# shema.net
KiCad netlist of a schematic drawn in Altium Designer
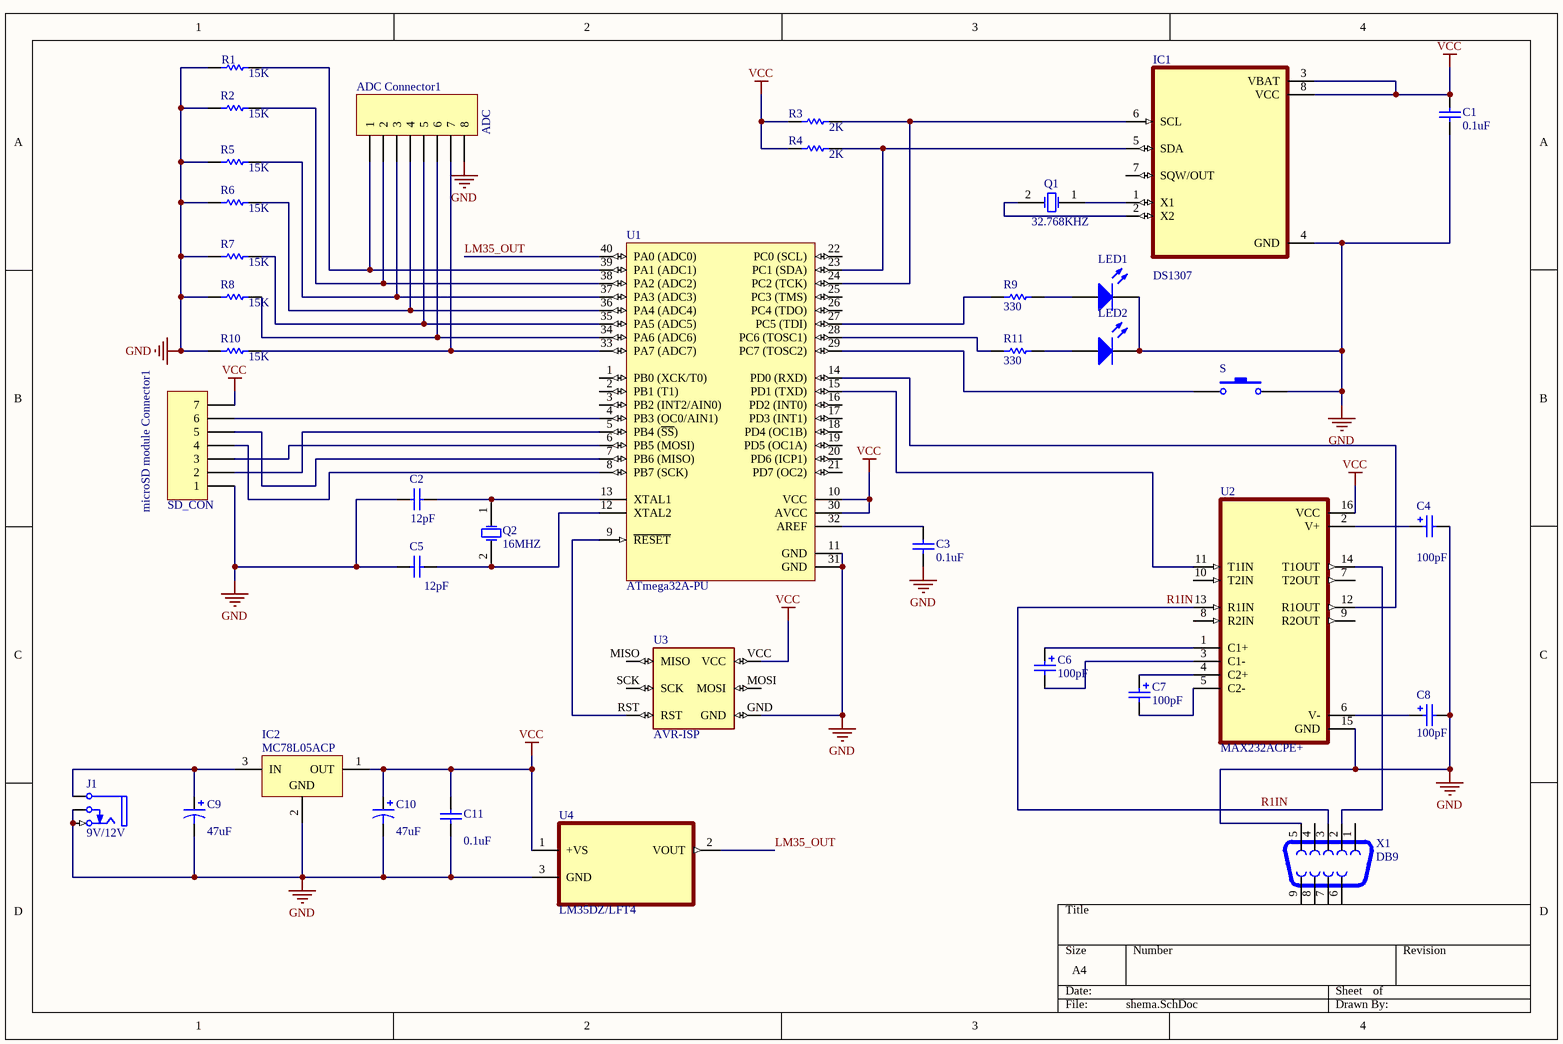
[diagram p0: shema.SchDoc]

(export (version "E")
  (design (tool "Eeschema 10.0.6"))
  (components
    (comp (ref "ADC Connector1")
      (value "ADC")
      (footprint "HDR1X8")
      (description "Header, 8-Pin")
      (fields (field (name "PUBLISHER") "Altium Limited"))
      (libsource (lib "Miscellaneous Connectors") (part "Header 8"))
    )
    (comp (ref "C1")
      (value "0.1uF")
      (footprint "RAD-0.3")
      (description "Capacitor")
      (fields (field (name "Comment") "Cap") (field (name "PUBLISHER") "Altium Limited"))
      (libsource (lib "Miscellaneous Devices") (part "Cap"))
    )
    (comp (ref "C2")
      (value "12pF")
      (footprint "RAD-0.3")
      (description "Capacitor")
      (fields (field (name "Comment") "Cap") (field (name "PUBLISHER") "Altium Limited"))
      (libsource (lib "Miscellaneous Devices") (part "Cap"))
    )
    (comp (ref "C3")
      (value "0.1uF")
      (footprint "RAD-0.3")
      (description "Capacitor")
      (fields (field (name "Comment") "Cap") (field (name "PUBLISHER") "Altium Limited"))
      (libsource (lib "Miscellaneous Devices") (part "Cap"))
    )
    (comp (ref "C4")
      (value "100pF")
      (footprint "POLAR0.8")
      (description "Polarized Capacitor (Axial)")
      (fields (field (name "Comment") "Cap Pol2") (field (name "PUBLISHER") "Altium Limited"))
      (libsource (lib "Miscellaneous Devices") (part "Cap Pol2"))
    )
    (comp (ref "C5")
      (value "12pF")
      (footprint "RAD-0.3")
      (description "Capacitor")
      (fields (field (name "Comment") "Cap") (field (name "PUBLISHER") "Altium Limited"))
      (libsource (lib "Miscellaneous Devices") (part "Cap"))
    )
    (comp (ref "C6")
      (value "100pF")
      (footprint "POLAR0.8")
      (description "Polarized Capacitor (Axial)")
      (fields (field (name "Comment") "Cap Pol2") (field (name "PUBLISHER") "Altium Limited"))
      (libsource (lib "Miscellaneous Devices") (part "Cap Pol2"))
    )
    (comp (ref "C7")
      (value "100pF")
      (footprint "POLAR0.8")
      (description "Polarized Capacitor (Axial)")
      (fields (field (name "Comment") "Cap Pol2") (field (name "PUBLISHER") "Altium Limited"))
      (libsource (lib "Miscellaneous Devices") (part "Cap Pol2"))
    )
    (comp (ref "C8")
      (value "100pF")
      (footprint "POLAR0.8")
      (description "Polarized Capacitor (Axial)")
      (fields (field (name "Comment") "Cap Pol2") (field (name "PUBLISHER") "Altium Limited"))
      (libsource (lib "Miscellaneous Devices") (part "Cap Pol2"))
    )
    (comp (ref "C9")
      (value "47uF")
      (footprint "RB7.6-15")
      (description "Polarized Capacitor (Radial)")
      (fields (field (name "Comment") "Cap Pol1") (field (name "PUBLISHER") "Altium Limited"))
      (libsource (lib "Miscellaneous Devices") (part "Cap Pol1"))
    )
    (comp (ref "C10")
      (value "47uF")
      (footprint "RB7.6-15")
      (description "Polarized Capacitor (Radial)")
      (fields (field (name "Comment") "Cap Pol1") (field (name "PUBLISHER") "Altium Limited"))
      (libsource (lib "Miscellaneous Devices") (part "Cap Pol1"))
    )
    (comp (ref "C11")
      (value "0.1uF")
      (footprint "RAD-0.3")
      (description "Capacitor")
      (fields (field (name "Comment") "Cap") (field (name "PUBLISHER") "Altium Limited"))
      (libsource (lib "Miscellaneous Devices") (part "Cap"))
    )
    (comp (ref "IC1")
      (value "DS1307")
      (footprint "DIP794W47P254L991H457Q8")
      (description "Real Time Clock (RTC) IC Clock/Calendar 56B IÂ²C, 2-Wire Serial 8-SOIC (0.154, 3.90mm Width)")
      (fields (field (name "MF") "Maxim Integrated"))
      (libsource (lib "DS1307") (part "DS1307"))
    )
    (comp (ref "IC2")
      (value "MC78L05ACP")
      (footprint "29-04")
      (description "3-Terminal Low-Current Positive Fixed Voltage Regulator")
      (fields (field (name "PUBLISHER") "Altium Limited"))
      (libsource (lib "Motorola Power Mgt Voltage Regulator") (part "MC78L05ACP"))
    )
    (comp (ref "J1")
      (value "9V/12V")
      (footprint "JACK/6-V3A")
      (description "Jack Socket, 1/4\" [6.5mm], Thru-Hole, Vertical, 2-Conductor with Tip closed")
      (fields (field (name "PUBLISHER") "Altium Limited"))
      (libsource (lib "Miscellaneous Connectors") (part "Phonejack2 TN"))
    )
    (comp (ref "LED1")
      (value "LED0")
      (footprint "LED-0")
      (description "Typical INFRARED GaAs LED")
      (fields (field (name "PUBLISHER") "Altium Limited"))
      (libsource (lib "Miscellaneous Devices") (part "LED0"))
    )
    (comp (ref "LED2")
      (value "LED0")
      (footprint "LED-0")
      (description "Typical INFRARED GaAs LED")
      (fields (field (name "PUBLISHER") "Altium Limited"))
      (libsource (lib "Miscellaneous Devices") (part "LED0"))
    )
    (comp (ref "microSD module Connector1")
      (value "SD_CON")
      (footprint "HDR1X7")
      (description "Header, 7-Pin")
      (fields (field (name "PUBLISHER") "Altium Limited"))
      (libsource (lib "Miscellaneous Connectors") (part "Header 7"))
    )
    (comp (ref "Q1")
      (value "XTAL")
      (footprint "R38")
      (description "Crystal Oscillator")
      (fields (field (name "FREQ") "32.768KHZ") (field (name "PUBLISHER") "Altium Limited"))
      (libsource (lib "Miscellaneous Devices") (part "XTAL"))
    )
    (comp (ref "Q2")
      (value "XTAL")
      (footprint "R38")
      (description "Crystal Oscillator")
      (fields (field (name "FREQ") "16MHZ") (field (name "PUBLISHER") "Altium Limited"))
      (libsource (lib "Miscellaneous Devices") (part "XTAL"))
    )
    (comp (ref "R1")
      (value "15K")
      (footprint "AXIAL-0.3")
      (description "Resistor")
      (fields (field (name "Comment") "Res1") (field (name "PUBLISHER") "Altium Limited"))
      (libsource (lib "Miscellaneous Devices") (part "Res1"))
    )
    (comp (ref "R2")
      (value "15K")
      (footprint "AXIAL-0.3")
      (description "Resistor")
      (fields (field (name "Comment") "Res1") (field (name "PUBLISHER") "Altium Limited"))
      (libsource (lib "Miscellaneous Devices") (part "Res1"))
    )
    (comp (ref "R3")
      (value "2K")
      (footprint "AXIAL-0.3")
      (description "Resistor")
      (fields (field (name "Comment") "Res1") (field (name "PUBLISHER") "Altium Limited"))
      (libsource (lib "Miscellaneous Devices") (part "Res1"))
    )
    (comp (ref "R4")
      (value "2K")
      (footprint "AXIAL-0.3")
      (description "Resistor")
      (fields (field (name "Comment") "Res1") (field (name "PUBLISHER") "Altium Limited"))
      (libsource (lib "Miscellaneous Devices") (part "Res1"))
    )
    (comp (ref "R5")
      (value "15K")
      (footprint "AXIAL-0.3")
      (description "Resistor")
      (fields (field (name "Comment") "Res1") (field (name "PUBLISHER") "Altium Limited"))
      (libsource (lib "Miscellaneous Devices") (part "Res1"))
    )
    (comp (ref "R6")
      (value "15K")
      (footprint "AXIAL-0.3")
      (description "Resistor")
      (fields (field (name "Comment") "Res1") (field (name "PUBLISHER") "Altium Limited"))
      (libsource (lib "Miscellaneous Devices") (part "Res1"))
    )
    (comp (ref "R7")
      (value "15K")
      (footprint "AXIAL-0.3")
      (description "Resistor")
      (fields (field (name "Comment") "Res1") (field (name "PUBLISHER") "Altium Limited"))
      (libsource (lib "Miscellaneous Devices") (part "Res1"))
    )
    (comp (ref "R8")
      (value "15K")
      (footprint "AXIAL-0.3")
      (description "Resistor")
      (fields (field (name "Comment") "Res1") (field (name "PUBLISHER") "Altium Limited"))
      (libsource (lib "Miscellaneous Devices") (part "Res1"))
    )
    (comp (ref "R9")
      (value "330")
      (footprint "AXIAL-0.3")
      (description "Resistor")
      (fields (field (name "Comment") "Res1") (field (name "PUBLISHER") "Altium Limited"))
      (libsource (lib "Miscellaneous Devices") (part "Res1"))
    )
    (comp (ref "R10")
      (value "15K")
      (footprint "AXIAL-0.3")
      (description "Resistor")
      (fields (field (name "Comment") "Res1") (field (name "PUBLISHER") "Altium Limited"))
      (libsource (lib "Miscellaneous Devices") (part "Res1"))
    )
    (comp (ref "R11")
      (value "330")
      (footprint "AXIAL-0.3")
      (description "Resistor")
      (fields (field (name "Comment") "Res1") (field (name "PUBLISHER") "Altium Limited"))
      (libsource (lib "Miscellaneous Devices") (part "Res1"))
    )
    (comp (ref "S")
      (value "SW-PB")
      (footprint "SPST-2")
      (description "Switch")
      (fields (field (name "PUBLISHER") "Altium Limited"))
      (libsource (lib "Miscellaneous Devices") (part "SW-PB"))
    )
    (comp (ref "U1")
      (value "ATmega32A-PU")
      (footprint "40P6")
      (fields (field (name "PUBLISHER") "Altium Limited"))
      (libsource (lib "Atmel Microcontroller 8-Bit megaAVR") (part "ATmega32A-PU"))
    )
    (comp (ref "U2")
      (value "MAX232ACPE+")
      (footprint "DIP794W47P254L1943H457Q16")
      (description "2/2 Transceiver Full RS232 16-PDIP")
      (fields (field (name "MP") "MAX232ACPE") (field (name "MF") "Maxim Integrated"))
      (libsource (lib "MAX232ACPE_") (part "MAX232ACPE+"))
    )
    (comp (ref "U3")
      (value "AVR-ISP")
      (footprint "AVR-ISP")
      (description "Emulators / Simulators AVR USB IN CIRCUIT EMUL/PRGMR ISP")
      (fields (field (name "MF") "Gravitech"))
      (libsource (lib "AVR-ISP") (part "AVR-ISP"))
    )
    (comp (ref "U4")
      (value "LM35DZ/LFT4")
      (footprint "TO127P254X495-3P")
      (description "&plusmn;0.5&deg;C 4V-30V, Temperature sensor with analog output 3-TO-92")
      (fields
        (field (name "MF") "Texas Instruments")
        (field (name "BUYPART") "https://www.snapeda.com/parts/LM35DZ/LFT4/Texas%20Instruments/view-part/19434/?ref=eda")
      )
      (libsource (lib "LM35DZ_LFT4") (part "LM35DZ/LFT4"))
    )
    (comp (ref "X1")
      (value "DB9")
      (footprint "DB9")
      (description "SURGE SUPPRESSOR RS-232 DB9M/F")
      (fields (field (name "MF") "Tripp Lite"))
      (libsource (lib "DB9") (part "DB9"))
    )
  )
  (nets
    (net (code "1") (name "/LM35_OUT") (class "Default")
      (node (ref "U1") (pin "40") (pinfunction "PA0_(ADC0)_40") (pintype "bidirectional"))
      (node (ref "U4") (pin "2") (pinfunction "VOUT_2") (pintype "output"))
    )
    (net (code "2") (name "/R1IN") (class "Default")
      (node (ref "U2") (pin "13") (pinfunction "R1IN_13") (pintype "input"))
      (node (ref "X1") (pin "3") (pinfunction "3_3") (pintype "passive"))
    )
    (net (code "3") (name "GND") (class "Default")
      (node (ref "ADC Connector1") (pin "8") (pinfunction "8_8") (pintype "passive"))
      (node (ref "C1") (pin "1") (pinfunction "1_1") (pintype "passive"))
      (node (ref "C10") (pin "2") (pinfunction "2_2") (pintype "passive"))
      (node (ref "C11") (pin "1") (pinfunction "1_1") (pintype "passive"))
      (node (ref "C2") (pin "1") (pinfunction "1_1") (pintype "passive"))
      (node (ref "C3") (pin "2") (pinfunction "2_2") (pintype "passive"))
      (node (ref "C4") (pin "2") (pinfunction "2_2") (pintype "passive"))
      (node (ref "C5") (pin "1") (pinfunction "1_1") (pintype "passive"))
      (node (ref "C8") (pin "2") (pinfunction "2_2") (pintype "passive"))
      (node (ref "C9") (pin "2") (pinfunction "2_2") (pintype "passive"))
      (node (ref "IC1") (pin "4") (pinfunction "GND_4") (pintype "power_in"))
      (node (ref "IC2") (pin "2") (pinfunction "GND_2") (pintype "power_in"))
      (node (ref "J1") (pin "1") (pinfunction "T_1") (pintype "input"))
      (node (ref "J1") (pin "2") (pinfunction "TN_2") (pintype "passive"))
      (node (ref "LED1") (pin "2") (pinfunction "K_2") (pintype "passive"))
      (node (ref "LED2") (pin "2") (pinfunction "K_2") (pintype "passive"))
      (node (ref "R1") (pin "1") (pinfunction "1_1") (pintype "passive"))
      (node (ref "R10") (pin "1") (pinfunction "1_1") (pintype "passive"))
      (node (ref "R2") (pin "1") (pinfunction "1_1") (pintype "passive"))
      (node (ref "R5") (pin "1") (pinfunction "1_1") (pintype "passive"))
      (node (ref "R6") (pin "1") (pinfunction "1_1") (pintype "passive"))
      (node (ref "R7") (pin "1") (pinfunction "1_1") (pintype "passive"))
      (node (ref "R8") (pin "1") (pinfunction "1_1") (pintype "passive"))
      (node (ref "S") (pin "2") (pinfunction "2_2") (pintype "passive"))
      (node (ref "U1") (pin "11") (pinfunction "GND_11") (pintype "power_in"))
      (node (ref "U1") (pin "31") (pinfunction "GND_31") (pintype "power_in"))
      (node (ref "U2") (pin "15") (pinfunction "GND_15") (pintype "power_in"))
      (node (ref "U3") (pin "GND") (pinfunction "GND_GND") (pintype "bidirectional"))
      (node (ref "U4") (pin "3") (pinfunction "GND_3") (pintype "passive"))
      (node (ref "X1") (pin "5") (pinfunction "5_5") (pintype "passive"))
      (node (ref "microSD module Connector1") (pin "1") (pinfunction "1_1") (pintype "passive"))
    )
    (net (code "4") (name "Net-(IC1-SCL)") (class "Default")
      (node (ref "IC1") (pin "6") (pinfunction "SCL_6") (pintype "input"))
      (node (ref "R3") (pin "2") (pinfunction "2_2") (pintype "passive"))
      (node (ref "U1") (pin "24") (pinfunction "PC2_(TCK)_24") (pintype "bidirectional"))
    )
    (net (code "5") (name "Net-(IC1-SDA)") (class "Default")
      (node (ref "IC1") (pin "5") (pinfunction "SDA_5") (pintype "bidirectional"))
      (node (ref "R4") (pin "2") (pinfunction "2_2") (pintype "passive"))
      (node (ref "U1") (pin "23") (pinfunction "PC1_(SDA)_23") (pintype "bidirectional"))
    )
    (net (code "6") (name "Net-(IC1-X1)") (class "Default")
      (node (ref "IC1") (pin "1") (pinfunction "X1_1") (pintype "bidirectional"))
      (node (ref "Q1") (pin "1") (pinfunction "OSC1_1") (pintype "passive"))
    )
    (net (code "7") (name "Net-(IC1-X2)") (class "Default")
      (node (ref "IC1") (pin "2") (pinfunction "X2_2") (pintype "bidirectional"))
      (node (ref "Q1") (pin "2") (pinfunction "OSC2_2") (pintype "passive"))
    )
    (net (code "8") (name "Net-(IC2-IN)") (class "Default")
      (node (ref "C9") (pin "1") (pinfunction "1_1") (pintype "passive"))
      (node (ref "IC2") (pin "3") (pinfunction "IN_3") (pintype "power_in"))
      (node (ref "J1") (pin "5") (pinfunction "S_5") (pintype "power_in"))
    )
    (net (code "9") (name "Net-(LED1-A)") (class "Default")
      (node (ref "LED1") (pin "1") (pinfunction "A_1") (pintype "passive"))
      (node (ref "R9") (pin "2") (pinfunction "2_2") (pintype "passive"))
    )
    (net (code "10") (name "Net-(LED2-A)") (class "Default")
      (node (ref "LED2") (pin "1") (pinfunction "A_1") (pintype "passive"))
      (node (ref "R11") (pin "2") (pinfunction "2_2") (pintype "passive"))
    )
    (net (code "11") (name "Net-(Q2-OSC1)") (class "Default")
      (node (ref "C2") (pin "2") (pinfunction "2_2") (pintype "passive"))
      (node (ref "Q2") (pin "1") (pinfunction "OSC1_1") (pintype "passive"))
      (node (ref "U1") (pin "13") (pinfunction "XTAL1_13") (pintype "passive"))
    )
    (net (code "12") (name "Net-(Q2-OSC2)") (class "Default")
      (node (ref "C5") (pin "2") (pinfunction "2_2") (pintype "passive"))
      (node (ref "Q2") (pin "2") (pinfunction "OSC2_2") (pintype "passive"))
      (node (ref "U1") (pin "12") (pinfunction "XTAL2_12") (pintype "passive"))
    )
    (net (code "13") (name "Net-(U1-AREF)") (class "Default")
      (node (ref "C3") (pin "1") (pinfunction "1_1") (pintype "passive"))
      (node (ref "U1") (pin "32") (pinfunction "AREF_32") (pintype "power_in"))
    )
    (net (code "14") (name "Net-(U1-PA1_(ADC1))") (class "Default")
      (node (ref "ADC Connector1") (pin "1") (pinfunction "1_1") (pintype "passive"))
      (node (ref "R1") (pin "2") (pinfunction "2_2") (pintype "passive"))
      (node (ref "U1") (pin "39") (pinfunction "PA1_(ADC1)_39") (pintype "bidirectional"))
    )
    (net (code "15") (name "Net-(U1-PA2_(ADC2))") (class "Default")
      (node (ref "ADC Connector1") (pin "2") (pinfunction "2_2") (pintype "passive"))
      (node (ref "R2") (pin "2") (pinfunction "2_2") (pintype "passive"))
      (node (ref "U1") (pin "38") (pinfunction "PA2_(ADC2)_38") (pintype "bidirectional"))
    )
    (net (code "16") (name "Net-(U1-PA3_(ADC3))") (class "Default")
      (node (ref "ADC Connector1") (pin "3") (pinfunction "3_3") (pintype "passive"))
      (node (ref "R5") (pin "2") (pinfunction "2_2") (pintype "passive"))
      (node (ref "U1") (pin "37") (pinfunction "PA3_(ADC3)_37") (pintype "bidirectional"))
    )
    (net (code "17") (name "Net-(U1-PA4_(ADC4))") (class "Default")
      (node (ref "ADC Connector1") (pin "4") (pinfunction "4_4") (pintype "passive"))
      (node (ref "R6") (pin "2") (pinfunction "2_2") (pintype "passive"))
      (node (ref "U1") (pin "36") (pinfunction "PA4_(ADC4)_36") (pintype "bidirectional"))
    )
    (net (code "18") (name "Net-(U1-PA5_(ADC5))") (class "Default")
      (node (ref "ADC Connector1") (pin "5") (pinfunction "5_5") (pintype "passive"))
      (node (ref "R7") (pin "2") (pinfunction "2_2") (pintype "passive"))
      (node (ref "U1") (pin "35") (pinfunction "PA5_(ADC5)_35") (pintype "bidirectional"))
    )
    (net (code "19") (name "Net-(U1-PA6_(ADC6))") (class "Default")
      (node (ref "ADC Connector1") (pin "6") (pinfunction "6_6") (pintype "passive"))
      (node (ref "R8") (pin "2") (pinfunction "2_2") (pintype "passive"))
      (node (ref "U1") (pin "34") (pinfunction "PA6_(ADC6)_34") (pintype "bidirectional"))
    )
    (net (code "20") (name "Net-(U1-PA7_(ADC7))") (class "Default")
      (node (ref "ADC Connector1") (pin "7") (pinfunction "7_7") (pintype "passive"))
      (node (ref "R10") (pin "2") (pinfunction "2_2") (pintype "passive"))
      (node (ref "U1") (pin "33") (pinfunction "PA7_(ADC7)_33") (pintype "bidirectional"))
    )
    (net (code "21") (name "Net-(U1-PB3_(OC0{slash}AIN1))") (class "Default")
      (node (ref "U1") (pin "4") (pinfunction "PB3_(OC0/AIN1)_4") (pintype "bidirectional"))
      (node (ref "microSD module Connector1") (pin "6") (pinfunction "6_6") (pintype "passive"))
    )
    (net (code "22") (name "Net-(U1-PB4_(~{SS}))") (class "Default")
      (node (ref "U1") (pin "5") (pinfunction "PB4_(~{SS})_5") (pintype "bidirectional"))
      (node (ref "microSD module Connector1") (pin "2") (pinfunction "2_2") (pintype "passive"))
    )
    (net (code "23") (name "Net-(U1-PB5_(MOSI))") (class "Default")
      (node (ref "U1") (pin "6") (pinfunction "PB5_(MOSI)_6") (pintype "bidirectional"))
      (node (ref "microSD module Connector1") (pin "3") (pinfunction "3_3") (pintype "passive"))
    )
    (net (code "24") (name "Net-(U1-PB6_(MISO))") (class "Default")
      (node (ref "U1") (pin "7") (pinfunction "PB6_(MISO)_7") (pintype "bidirectional"))
      (node (ref "microSD module Connector1") (pin "5") (pinfunction "5_5") (pintype "passive"))
    )
    (net (code "25") (name "Net-(U1-PB7_(SCK))") (class "Default")
      (node (ref "U1") (pin "8") (pinfunction "PB7_(SCK)_8") (pintype "bidirectional"))
      (node (ref "microSD module Connector1") (pin "4") (pinfunction "4_4") (pintype "passive"))
    )
    (net (code "26") (name "Net-(U1-PC5_(TDI))") (class "Default")
      (node (ref "R9") (pin "1") (pinfunction "1_1") (pintype "passive"))
      (node (ref "U1") (pin "27") (pinfunction "PC5_(TDI)_27") (pintype "bidirectional"))
    )
    (net (code "27") (name "Net-(U1-PC6_(TOSC1))") (class "Default")
      (node (ref "R11") (pin "1") (pinfunction "1_1") (pintype "passive"))
      (node (ref "U1") (pin "28") (pinfunction "PC6_(TOSC1)_28") (pintype "bidirectional"))
    )
    (net (code "28") (name "Net-(U1-PC7_(TOSC2))") (class "Default")
      (node (ref "S") (pin "1") (pinfunction "1_1") (pintype "passive"))
      (node (ref "U1") (pin "29") (pinfunction "PC7_(TOSC2)_29") (pintype "bidirectional"))
    )
    (net (code "29") (name "Net-(U1-PD0_(RXD))") (class "Default")
      (node (ref "U1") (pin "14") (pinfunction "PD0_(RXD)_14") (pintype "bidirectional"))
      (node (ref "U2") (pin "12") (pinfunction "R1OUT_12") (pintype "output"))
    )
    (net (code "30") (name "Net-(U1-PD1_(TXD))") (class "Default")
      (node (ref "U1") (pin "15") (pinfunction "PD1_(TXD)_15") (pintype "bidirectional"))
      (node (ref "U2") (pin "11") (pinfunction "T1IN_11") (pintype "input"))
    )
    (net (code "31") (name "Net-(U1-~{RESET})") (class "Default")
      (node (ref "U1") (pin "9") (pinfunction "~{RESET}_9") (pintype "input"))
      (node (ref "U3") (pin "RST") (pinfunction "RST_RST") (pintype "bidirectional"))
    )
    (net (code "32") (name "Net-(U2-C1+)") (class "Default")
      (node (ref "C6") (pin "1") (pinfunction "1_1") (pintype "passive"))
      (node (ref "U2") (pin "1") (pinfunction "C1+_1") (pintype "passive"))
    )
    (net (code "33") (name "Net-(U2-C1-)") (class "Default")
      (node (ref "C6") (pin "2") (pinfunction "2_2") (pintype "passive"))
      (node (ref "U2") (pin "3") (pinfunction "C1-_3") (pintype "passive"))
    )
    (net (code "34") (name "Net-(U2-C2+)") (class "Default")
      (node (ref "C7") (pin "1") (pinfunction "1_1") (pintype "passive"))
      (node (ref "U2") (pin "4") (pinfunction "C2+_4") (pintype "passive"))
    )
    (net (code "35") (name "Net-(U2-C2-)") (class "Default")
      (node (ref "C7") (pin "2") (pinfunction "2_2") (pintype "passive"))
      (node (ref "U2") (pin "5") (pinfunction "C2-_5") (pintype "passive"))
    )
    (net (code "36") (name "Net-(U2-T1OUT)") (class "Default")
      (node (ref "U2") (pin "14") (pinfunction "T1OUT_14") (pintype "output"))
      (node (ref "X1") (pin "2") (pinfunction "2_2") (pintype "passive"))
    )
    (net (code "37") (name "Net-(U2-V+)") (class "Default")
      (node (ref "C4") (pin "1") (pinfunction "1_1") (pintype "passive"))
      (node (ref "U2") (pin "2") (pinfunction "V+_2") (pintype "power_in"))
    )
    (net (code "38") (name "Net-(U2-V-)") (class "Default")
      (node (ref "C8") (pin "1") (pinfunction "1_1") (pintype "passive"))
      (node (ref "U2") (pin "6") (pinfunction "V-_6") (pintype "power_in"))
    )
    (net (code "39") (name "VCC") (class "Default")
      (node (ref "C1") (pin "2") (pinfunction "2_2") (pintype "passive"))
      (node (ref "C10") (pin "1") (pinfunction "1_1") (pintype "passive"))
      (node (ref "C11") (pin "2") (pinfunction "2_2") (pintype "passive"))
      (node (ref "IC1") (pin "3") (pinfunction "VBAT_3") (pintype "power_in"))
      (node (ref "IC1") (pin "8") (pinfunction "VCC_8") (pintype "power_in"))
      (node (ref "IC2") (pin "1") (pinfunction "OUT_1") (pintype "power_in"))
      (node (ref "R3") (pin "1") (pinfunction "1_1") (pintype "passive"))
      (node (ref "R4") (pin "1") (pinfunction "1_1") (pintype "passive"))
      (node (ref "U1") (pin "10") (pinfunction "VCC_10") (pintype "power_in"))
      (node (ref "U1") (pin "30") (pinfunction "AVCC_30") (pintype "power_in"))
      (node (ref "U2") (pin "16") (pinfunction "VCC_16") (pintype "power_in"))
      (node (ref "U3") (pin "VCC") (pinfunction "VCC_VCC") (pintype "bidirectional"))
      (node (ref "U4") (pin "1") (pinfunction "+VS_1") (pintype "power_in"))
      (node (ref "microSD module Connector1") (pin "7") (pinfunction "7_7") (pintype "passive"))
    )
    (net (code "40") (name "unconnected-(IC1-SQW{slash}OUT-Pad7)") (class "Default")
      (node (ref "IC1") (pin "7") (pinfunction "SQW/OUT_7") (pintype "bidirectional"))
    )
    (net (code "41") (name "unconnected-(U1-PB0_(XCK{slash}T0)-Pad1)") (class "Default")
      (node (ref "U1") (pin "1") (pinfunction "PB0_(XCK/T0)_1") (pintype "bidirectional"))
    )
    (net (code "42") (name "unconnected-(U1-PB1_(T1)-Pad2)") (class "Default")
      (node (ref "U1") (pin "2") (pinfunction "PB1_(T1)_2") (pintype "bidirectional"))
    )
    (net (code "43") (name "unconnected-(U1-PB2_(INT2{slash}AIN0)-Pad3)") (class "Default")
      (node (ref "U1") (pin "3") (pinfunction "PB2_(INT2/AIN0)_3") (pintype "bidirectional"))
    )
    (net (code "44") (name "unconnected-(U1-PC0_(SCL)-Pad22)") (class "Default")
      (node (ref "U1") (pin "22") (pinfunction "PC0_(SCL)_22") (pintype "bidirectional"))
    )
    (net (code "45") (name "unconnected-(U1-PC3_(TMS)-Pad25)") (class "Default")
      (node (ref "U1") (pin "25") (pinfunction "PC3_(TMS)_25") (pintype "bidirectional"))
    )
    (net (code "46") (name "unconnected-(U1-PC4_(TDO)-Pad26)") (class "Default")
      (node (ref "U1") (pin "26") (pinfunction "PC4_(TDO)_26") (pintype "bidirectional"))
    )
    (net (code "47") (name "unconnected-(U1-PD2_(INT0)-Pad16)") (class "Default")
      (node (ref "U1") (pin "16") (pinfunction "PD2_(INT0)_16") (pintype "bidirectional"))
    )
    (net (code "48") (name "unconnected-(U1-PD3_(INT1)-Pad17)") (class "Default")
      (node (ref "U1") (pin "17") (pinfunction "PD3_(INT1)_17") (pintype "bidirectional"))
    )
    (net (code "49") (name "unconnected-(U1-PD4_(OC1B)-Pad18)") (class "Default")
      (node (ref "U1") (pin "18") (pinfunction "PD4_(OC1B)_18") (pintype "bidirectional"))
    )
    (net (code "50") (name "unconnected-(U1-PD5_(OC1A)-Pad19)") (class "Default")
      (node (ref "U1") (pin "19") (pinfunction "PD5_(OC1A)_19") (pintype "bidirectional"))
    )
    (net (code "51") (name "unconnected-(U1-PD6_(ICP1)-Pad20)") (class "Default")
      (node (ref "U1") (pin "20") (pinfunction "PD6_(ICP1)_20") (pintype "bidirectional"))
    )
    (net (code "52") (name "unconnected-(U1-PD7_(OC2)-Pad21)") (class "Default")
      (node (ref "U1") (pin "21") (pinfunction "PD7_(OC2)_21") (pintype "bidirectional"))
    )
    (net (code "53") (name "unconnected-(U2-R2IN-Pad8)") (class "Default")
      (node (ref "U2") (pin "8") (pinfunction "R2IN_8") (pintype "input"))
    )
    (net (code "54") (name "unconnected-(U2-R2OUT-Pad9)") (class "Default")
      (node (ref "U2") (pin "9") (pinfunction "R2OUT_9") (pintype "output"))
    )
    (net (code "55") (name "unconnected-(U2-T2IN-Pad10)") (class "Default")
      (node (ref "U2") (pin "10") (pinfunction "T2IN_10") (pintype "input"))
    )
    (net (code "56") (name "unconnected-(U2-T2OUT-Pad7)") (class "Default")
      (node (ref "U2") (pin "7") (pinfunction "T2OUT_7") (pintype "output"))
    )
    (net (code "57") (name "unconnected-(U3-PadMISO)") (class "Default")
      (node (ref "U3") (pin "MISO") (pinfunction "MISO_MISO") (pintype "bidirectional"))
    )
    (net (code "58") (name "unconnected-(U3-PadMOSI)") (class "Default")
      (node (ref "U3") (pin "MOSI") (pinfunction "MOSI_MOSI") (pintype "bidirectional"))
    )
    (net (code "59") (name "unconnected-(U3-PadSCK)") (class "Default")
      (node (ref "U3") (pin "SCK") (pinfunction "SCK_SCK") (pintype "bidirectional"))
    )
    (net (code "60") (name "unconnected-(X1-Pad1)") (class "Default")
      (node (ref "X1") (pin "1") (pinfunction "1_1") (pintype "passive"))
    )
    (net (code "61") (name "unconnected-(X1-Pad4)") (class "Default")
      (node (ref "X1") (pin "4") (pinfunction "4_4") (pintype "passive"))
    )
    (net (code "62") (name "unconnected-(X1-Pad6)") (class "Default")
      (node (ref "X1") (pin "6") (pinfunction "6_6") (pintype "passive"))
    )
    (net (code "63") (name "unconnected-(X1-Pad7)") (class "Default")
      (node (ref "X1") (pin "7") (pinfunction "7_7") (pintype "passive"))
    )
    (net (code "64") (name "unconnected-(X1-Pad8)") (class "Default")
      (node (ref "X1") (pin "8") (pinfunction "8_8") (pintype "passive"))
    )
    (net (code "65") (name "unconnected-(X1-Pad9)") (class "Default")
      (node (ref "X1") (pin "9") (pinfunction "9_9") (pintype "passive"))
    )
  )
)
